# design.net
KiCad netlist of a schematic drawn in Altium Designer
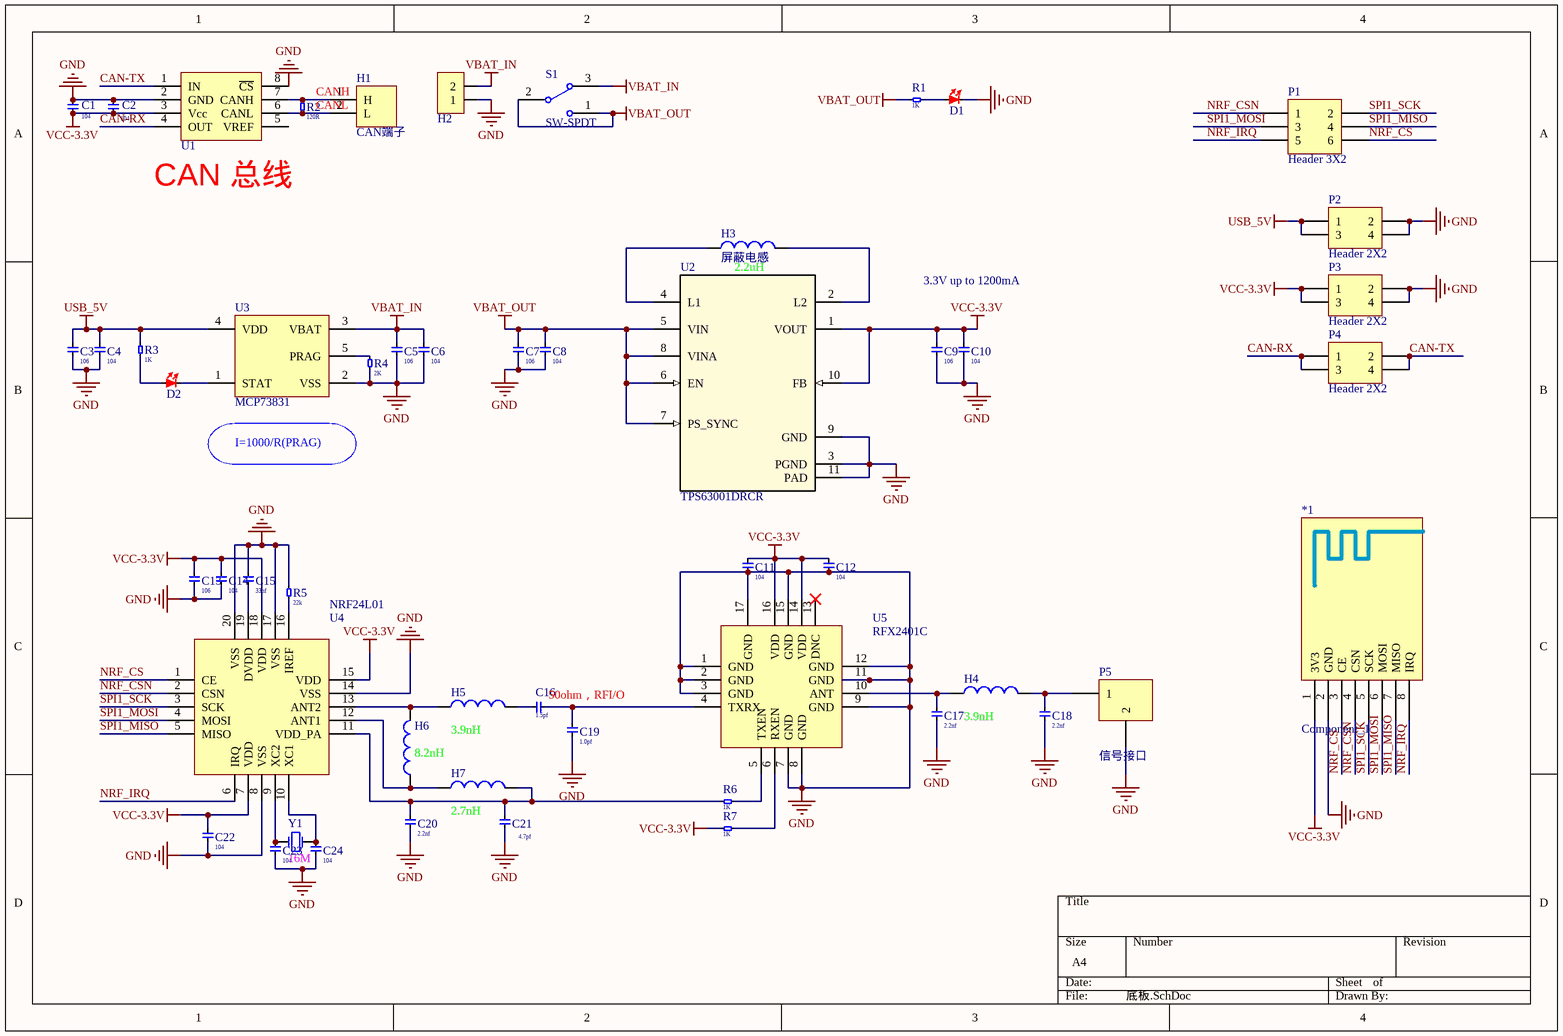
[diagram p0: 底板.SchDoc]

(export (version "E")
  (design (tool "Eeschema 10.0.6"))
  (components
    (comp (ref "*1")
      (value "Component_1")
      (footprint "PCBComponent_1")
      (libsource (lib "NRF2104") (part "Component_1"))
    )
    (comp (ref "C1")
      (value "CAP0603")
      (footprint "CAP0603")
      (fields (field (name "ALTIUM_UNNAMED_1") "104"))
      (libsource (lib "固执啊啊啊啊啊（方林的封装库）7.24") (part "CAP0603"))
    )
    (comp (ref "C2")
      (value "CAP0603")
      (footprint "CAP0603")
      (fields (field (name "ALTIUM_UNNAMED_1") "104"))
      (libsource (lib "固执啊啊啊啊啊（方林的封装库）7.24") (part "CAP0603"))
    )
    (comp (ref "C3")
      (value "CAP0603")
      (footprint "CAP0603")
      (fields (field (name "ALTIUM_UNNAMED_1") "106"))
      (libsource (lib "固执啊啊啊啊啊（方林的封装库）7.24") (part "CAP0603"))
    )
    (comp (ref "C4")
      (value "CAP0603")
      (footprint "CAP0603")
      (fields (field (name "ALTIUM_UNNAMED_1") "104"))
      (libsource (lib "固执啊啊啊啊啊（方林的封装库）7.24") (part "CAP0603"))
    )
    (comp (ref "C5")
      (value "CAP0603")
      (footprint "CAP0603")
      (fields (field (name "ALTIUM_UNNAMED_1") "106"))
      (libsource (lib "固执啊啊啊啊啊（方林的封装库）7.24") (part "CAP0603"))
    )
    (comp (ref "C6")
      (value "CAP0603")
      (footprint "CAP0603")
      (fields (field (name "ALTIUM_UNNAMED_1") "104"))
      (libsource (lib "固执啊啊啊啊啊（方林的封装库）7.24") (part "CAP0603"))
    )
    (comp (ref "C7")
      (value "CAP0603")
      (footprint "CAP0603")
      (fields (field (name "ALTIUM_UNNAMED_1") "106"))
      (libsource (lib "固执啊啊啊啊啊（方林的封装库）7.24") (part "CAP0603"))
    )
    (comp (ref "C8")
      (value "CAP0603")
      (footprint "CAP0603")
      (fields (field (name "ALTIUM_UNNAMED_1") "104"))
      (libsource (lib "固执啊啊啊啊啊（方林的封装库）7.24") (part "CAP0603"))
    )
    (comp (ref "C9")
      (value "CAP0603")
      (footprint "CAP0603")
      (fields (field (name "ALTIUM_UNNAMED_1") "106"))
      (libsource (lib "固执啊啊啊啊啊（方林的封装库）7.24") (part "CAP0603"))
    )
    (comp (ref "C10")
      (value "CAP0603")
      (footprint "CAP0603")
      (fields (field (name "ALTIUM_UNNAMED_1") "104"))
      (libsource (lib "固执啊啊啊啊啊（方林的封装库）7.24") (part "CAP0603"))
    )
    (comp (ref "C11")
      (value "CAP0603")
      (footprint "CAP0603")
      (fields (field (name "ALTIUM_UNNAMED_1") "104"))
      (libsource (lib "固执啊啊啊啊啊（方林的封装库）7.24") (part "CAP0603"))
    )
    (comp (ref "C12")
      (value "CAP0603")
      (footprint "CAP0603")
      (fields (field (name "ALTIUM_UNNAMED_1") "104"))
      (libsource (lib "固执啊啊啊啊啊（方林的封装库）7.24") (part "CAP0603"))
    )
    (comp (ref "C13")
      (value "CAP0603")
      (footprint "CAP0603")
      (fields (field (name "ALTIUM_UNNAMED_1") "106"))
      (libsource (lib "固执啊啊啊啊啊（方林的封装库）7.24") (part "CAP0603"))
    )
    (comp (ref "C14")
      (value "CAP0603")
      (footprint "CAP0603")
      (fields (field (name "ALTIUM_UNNAMED_1") "104"))
      (libsource (lib "固执啊啊啊啊啊（方林的封装库）7.24") (part "CAP0603"))
    )
    (comp (ref "C15")
      (value "CAP0603")
      (footprint "CAP0603")
      (fields (field (name "ALTIUM_UNNAMED_1") "33nf"))
      (libsource (lib "固执啊啊啊啊啊（方林的封装库）7.24") (part "CAP0603"))
    )
    (comp (ref "C16")
      (value "CAP0603")
      (footprint "CAP0603")
      (fields (field (name "ALTIUM_UNNAMED_1") "1.5pf"))
      (libsource (lib "固执啊啊啊啊啊（方林的封装库）7.24") (part "CAP0603"))
    )
    (comp (ref "C17")
      (value "CAP0603")
      (footprint "CAP0603")
      (fields (field (name "ALTIUM_UNNAMED_1") "2.2nf"))
      (libsource (lib "固执啊啊啊啊啊（方林的封装库）7.24") (part "CAP0603"))
    )
    (comp (ref "C18")
      (value "CAP0603")
      (footprint "CAP0603")
      (fields (field (name "ALTIUM_UNNAMED_1") "2.2nf"))
      (libsource (lib "固执啊啊啊啊啊（方林的封装库）7.24") (part "CAP0603"))
    )
    (comp (ref "C19")
      (value "CAP0603")
      (footprint "CAP0603")
      (fields (field (name "ALTIUM_UNNAMED_1") "1.0pf"))
      (libsource (lib "固执啊啊啊啊啊（方林的封装库）7.24") (part "CAP0603"))
    )
    (comp (ref "C20")
      (value "CAP0603")
      (footprint "CAP0603")
      (fields (field (name "ALTIUM_UNNAMED_1") "2.2nf"))
      (libsource (lib "固执啊啊啊啊啊（方林的封装库）7.24") (part "CAP0603"))
    )
    (comp (ref "C21")
      (value "CAP0603")
      (footprint "CAP0603")
      (fields (field (name "ALTIUM_UNNAMED_1") "4.7pf"))
      (libsource (lib "固执啊啊啊啊啊（方林的封装库）7.24") (part "CAP0603"))
    )
    (comp (ref "C22")
      (value "CAP0603")
      (footprint "CAP0603")
      (fields (field (name "ALTIUM_UNNAMED_1") "104"))
      (libsource (lib "固执啊啊啊啊啊（方林的封装库）7.24") (part "CAP0603"))
    )
    (comp (ref "C23")
      (value "CAP0603")
      (footprint "CAP0603")
      (fields (field (name "ALTIUM_UNNAMED_1") "104"))
      (libsource (lib "固执啊啊啊啊啊（方林的封装库）7.24") (part "CAP0603"))
    )
    (comp (ref "C24")
      (value "CAP0603")
      (footprint "CAP0603")
      (fields (field (name "ALTIUM_UNNAMED_1") "104"))
      (libsource (lib "固执啊啊啊啊啊（方林的封装库）7.24") (part "CAP0603"))
    )
    (comp (ref "D1")
      (value "LED")
      (footprint "LED_0603_B")
      (libsource (lib "固执啊啊啊啊啊（方林的封装库）7.24") (part "LED"))
    )
    (comp (ref "D2")
      (value "LED")
      (footprint "LED_0603_B")
      (libsource (lib "固执啊啊啊啊啊（方林的封装库）7.24") (part "LED"))
    )
    (comp (ref "H1")
      (value "CAN端子")
      (footprint "CAN端子")
      (libsource (lib "固执啊啊啊啊啊（方林的封装库）7.24") (part "CAN端子"))
    )
    (comp (ref "H2")
      (value "H2")
      (footprint "H2_WHITE")
      (description "排针")
      (libsource (lib "xiaoze_Library") (part "H2"))
    )
    (comp (ref "H3")
      (value "屏蔽电感")
      (footprint "屏蔽7.2*7.2")
      (fields (field (name "ALTIUM_UNNAMED_1") "2.2uH"))
      (libsource (lib "固执啊啊啊啊啊（方林的封装库）7.24") (part "屏蔽电感"))
    )
    (comp (ref "H4")
      (value "屏蔽电感")
      (footprint "CAP0603")
      (fields (field (name "ALTIUM_UNNAMED_1") "3.9nH"))
      (libsource (lib "固执啊啊啊啊啊（方林的封装库）7.24") (part "屏蔽电感"))
    )
    (comp (ref "H5")
      (value "屏蔽电感")
      (footprint "CAP0603")
      (fields (field (name "ALTIUM_UNNAMED_1") "3.9nH"))
      (libsource (lib "固执啊啊啊啊啊（方林的封装库）7.24") (part "屏蔽电感"))
    )
    (comp (ref "H6")
      (value "屏蔽电感")
      (footprint "CAP0603")
      (fields (field (name "ALTIUM_UNNAMED_1") "8.2nH"))
      (libsource (lib "固执啊啊啊啊啊（方林的封装库）7.24") (part "屏蔽电感"))
    )
    (comp (ref "H7")
      (value "屏蔽电感")
      (footprint "CAP0603")
      (fields (field (name "ALTIUM_UNNAMED_1") "2.7nH"))
      (libsource (lib "固执啊啊啊啊啊（方林的封装库）7.24") (part "屏蔽电感"))
    )
    (comp (ref "P1")
      (value "Header 3X2")
      (footprint "HDR2X3")
      (description "Header, 3-Pin, Dual row")
      (fields (field (name "PUBLISHER") "Altium Limited"))
      (libsource (lib "Miscellaneous Connectors") (part "Header 3X2"))
    )
    (comp (ref "P2")
      (value "Header 2X2")
      (footprint "HDR2X2")
      (description "Header, 2-Pin, Dual row")
      (fields (field (name "PUBLISHER") "Altium Limited"))
      (libsource (lib "Miscellaneous Connectors") (part "Header 2X2"))
    )
    (comp (ref "P3")
      (value "Header 2X2")
      (footprint "HDR2X2")
      (description "Header, 2-Pin, Dual row")
      (fields (field (name "PUBLISHER") "Altium Limited"))
      (libsource (lib "Miscellaneous Connectors") (part "Header 2X2"))
    )
    (comp (ref "P4")
      (value "Header 2X2")
      (footprint "HDR2X2")
      (description "Header, 2-Pin, Dual row")
      (fields (field (name "PUBLISHER") "Altium Limited"))
      (libsource (lib "Miscellaneous Connectors") (part "Header 2X2"))
    )
    (comp (ref "P5")
      (value "信号接口")
      (footprint "SMA-偏脚")
      (fields (field (name "PUBLISHER") "Altium Limited"))
      (libsource (lib "遥控器的封装") (part "SMA偏脚"))
    )
    (comp (ref "R1")
      (value "电阻R")
      (footprint "R0603")
      (fields (field (name "ALTIUM_UNNAMED_1") "1K"))
      (libsource (lib "固执啊啊啊啊啊（方林的封装库）7.24") (part "电阻R"))
    )
    (comp (ref "R2")
      (value "电阻R")
      (footprint "R0603")
      (fields (field (name "ALTIUM_UNNAMED_1") "120R"))
      (libsource (lib "固执啊啊啊啊啊（方林的封装库）7.24") (part "电阻R"))
    )
    (comp (ref "R3")
      (value "电阻R")
      (footprint "R0603")
      (fields (field (name "ALTIUM_UNNAMED_1") "1K"))
      (libsource (lib "固执啊啊啊啊啊（方林的封装库）7.24") (part "电阻R"))
    )
    (comp (ref "R4")
      (value "电阻R")
      (footprint "R0603")
      (fields (field (name "ALTIUM_UNNAMED_1") "2K"))
      (libsource (lib "固执啊啊啊啊啊（方林的封装库）7.24") (part "电阻R"))
    )
    (comp (ref "R5")
      (value "电阻R")
      (footprint "R0603")
      (fields (field (name "ALTIUM_UNNAMED_1") "22k"))
      (libsource (lib "固执啊啊啊啊啊（方林的封装库）7.24") (part "电阻R"))
    )
    (comp (ref "R6")
      (value "电阻R")
      (footprint "R0603")
      (fields (field (name "ALTIUM_UNNAMED_1") "1K"))
      (libsource (lib "固执啊啊啊啊啊（方林的封装库）7.24") (part "电阻R"))
    )
    (comp (ref "R7")
      (value "电阻R")
      (footprint "R0603")
      (fields (field (name "ALTIUM_UNNAMED_1") "1K"))
      (libsource (lib "固执啊啊啊啊啊（方林的封装库）7.24") (part "电阻R"))
    )
    (comp (ref "S1")
      (value "SW-SPDT")
      (footprint "SWITCH_A2")
      (description "开关")
      (fields (field (name "PUBLISHER") "Altium Limited"))
      (libsource (lib "Fszhang") (part "SW-SPDT"))
    )
    (comp (ref "U1")
      (value "VP230")
      (footprint "VP230")
      (description "CAN 芯片")
      (libsource (lib "固执啊啊啊啊啊（方林的封装库）7.24") (part "VP230"))
    )
    (comp (ref "U2")
      (value "TPS63001DRCR")
      (footprint "TPS63001")
      (description "Imported")
      (fields
        (field (name "ALTERNATE_PARTNUMBER") "TPS63001DRCT")
        (field (name "MANUFACTURER") "Texas Instruments")
      )
      (libsource (lib "遥控器的封装") (part "TPS63001DRCR"))
    )
    (comp (ref "U3") (value "MCP73831") (footprint "SOT-23-5") (libsource (lib "遥控器的封装") (part "MCP73831")))
    (comp (ref "U4")
      (value "NRF24L01")
      (footprint "QFN50P400X400X85_HS-21N")
      (libsource (lib "遥控器的封装") (part "NRF24L01_1"))
    )
    (comp (ref "U5")
      (value "RFX2401C")
      (footprint "QFN50P300X300X55_HS-17N")
      (libsource (lib "遥控器的封装") (part "RFX2401C"))
    )
    (comp (ref "Y1")
      (value "XTAL")
      (footprint "XTAL")
      (description "晶振")
      (fields (field (name "ALTIUM_UNNAMED_1") "16M"))
      (libsource (lib "固执啊啊啊啊啊（方林的封装库）7.24") (part "XTAL"))
    )
  )
  (nets
    (net (code "1") (name "/CAN-RX") (class "Default")
      (node (ref "P4") (pin "1") (pinfunction "1_1") (pintype "passive"))
      (node (ref "P4") (pin "3") (pinfunction "3_3") (pintype "passive"))
      (node (ref "U1") (pin "4") (pinfunction "OUT_4") (pintype "passive"))
    )
    (net (code "2") (name "/CAN-TX") (class "Default")
      (node (ref "P4") (pin "2") (pinfunction "2_2") (pintype "passive"))
      (node (ref "P4") (pin "4") (pinfunction "4_4") (pintype "passive"))
      (node (ref "U1") (pin "1") (pinfunction "IN_1") (pintype "passive"))
    )
    (net (code "3") (name "/CANH") (class "Default")
      (node (ref "H1") (pin "1") (pinfunction "H_1") (pintype "passive"))
      (node (ref "R2") (pin "2") (pintype "passive"))
      (node (ref "U1") (pin "7") (pinfunction "CANH_7") (pintype "passive"))
    )
    (net (code "4") (name "/CANL") (class "Default")
      (node (ref "H1") (pin "2") (pinfunction "L_2") (pintype "passive"))
      (node (ref "R2") (pin "1") (pintype "passive"))
      (node (ref "U1") (pin "6") (pinfunction "CANL_6") (pintype "passive"))
    )
    (net (code "5") (name "/NRF_CS") (class "Default")
      (node (ref "*1") (pin "3") (pinfunction "CE_3") (pintype "passive"))
      (node (ref "P1") (pin "6") (pinfunction "6_6") (pintype "passive"))
      (node (ref "U4") (pin "1") (pinfunction "CE_1") (pintype "passive"))
    )
    (net (code "6") (name "/NRF_CSN") (class "Default")
      (node (ref "*1") (pin "4") (pinfunction "CSN_4") (pintype "passive"))
      (node (ref "P1") (pin "1") (pinfunction "1_1") (pintype "passive"))
      (node (ref "U4") (pin "2") (pinfunction "CSN_2") (pintype "passive"))
    )
    (net (code "7") (name "/NRF_IRQ") (class "Default")
      (node (ref "*1") (pin "8") (pinfunction "IRQ_8") (pintype "passive"))
      (node (ref "P1") (pin "5") (pinfunction "5_5") (pintype "passive"))
      (node (ref "U4") (pin "6") (pinfunction "IRQ_6") (pintype "passive"))
    )
    (net (code "8") (name "/SPI1_MISO") (class "Default")
      (node (ref "*1") (pin "7") (pinfunction "MISO_7") (pintype "passive"))
      (node (ref "P1") (pin "4") (pinfunction "4_4") (pintype "passive"))
      (node (ref "U4") (pin "5") (pinfunction "MISO_5") (pintype "passive"))
    )
    (net (code "9") (name "/SPI1_MOSI") (class "Default")
      (node (ref "*1") (pin "6") (pinfunction "MOSI_6") (pintype "passive"))
      (node (ref "P1") (pin "3") (pinfunction "3_3") (pintype "passive"))
      (node (ref "U4") (pin "4") (pinfunction "MOSI_4") (pintype "passive"))
    )
    (net (code "10") (name "/SPI1_SCK") (class "Default")
      (node (ref "*1") (pin "5") (pinfunction "SCK_5") (pintype "passive"))
      (node (ref "P1") (pin "2") (pinfunction "2_2") (pintype "passive"))
      (node (ref "U4") (pin "3") (pinfunction "SCK_3") (pintype "passive"))
    )
    (net (code "11") (name "GND") (class "Default")
      (node (ref "*1") (pin "2") (pinfunction "GND_2") (pintype "passive"))
      (node (ref "C1") (pin "2") (pinfunction "2_2") (pintype "passive"))
      (node (ref "C10") (pin "1") (pinfunction "1_1") (pintype "passive"))
      (node (ref "C11") (pin "1") (pinfunction "1_1") (pintype "passive"))
      (node (ref "C12") (pin "1") (pinfunction "1_1") (pintype "passive"))
      (node (ref "C13") (pin "1") (pinfunction "1_1") (pintype "passive"))
      (node (ref "C14") (pin "1") (pinfunction "1_1") (pintype "passive"))
      (node (ref "C15") (pin "2") (pinfunction "2_2") (pintype "passive"))
      (node (ref "C17") (pin "1") (pinfunction "1_1") (pintype "passive"))
      (node (ref "C18") (pin "1") (pinfunction "1_1") (pintype "passive"))
      (node (ref "C19") (pin "2") (pinfunction "2_2") (pintype "passive"))
      (node (ref "C2") (pin "2") (pinfunction "2_2") (pintype "passive"))
      (node (ref "C20") (pin "2") (pinfunction "2_2") (pintype "passive"))
      (node (ref "C21") (pin "2") (pinfunction "2_2") (pintype "passive"))
      (node (ref "C22") (pin "1") (pinfunction "1_1") (pintype "passive"))
      (node (ref "C23") (pin "1") (pinfunction "1_1") (pintype "passive"))
      (node (ref "C24") (pin "1") (pinfunction "1_1") (pintype "passive"))
      (node (ref "C3") (pin "1") (pinfunction "1_1") (pintype "passive"))
      (node (ref "C4") (pin "1") (pinfunction "1_1") (pintype "passive"))
      (node (ref "C5") (pin "1") (pinfunction "1_1") (pintype "passive"))
      (node (ref "C6") (pin "1") (pinfunction "1_1") (pintype "passive"))
      (node (ref "C7") (pin "1") (pinfunction "1_1") (pintype "passive"))
      (node (ref "C8") (pin "1") (pinfunction "1_1") (pintype "passive"))
      (node (ref "C9") (pin "1") (pinfunction "1_1") (pintype "passive"))
      (node (ref "D1") (pin "2") (pintype "passive"))
      (node (ref "H2") (pin "1") (pinfunction "1_1") (pintype "passive"))
      (node (ref "P2") (pin "2") (pinfunction "2_2") (pintype "passive"))
      (node (ref "P2") (pin "4") (pinfunction "4_4") (pintype "passive"))
      (node (ref "P3") (pin "2") (pinfunction "2_2") (pintype "passive"))
      (node (ref "P3") (pin "4") (pinfunction "4_4") (pintype "passive"))
      (node (ref "P5") (pin "2") (pinfunction "2_2") (pintype "passive"))
      (node (ref "R4") (pin "1") (pintype "passive"))
      (node (ref "R5") (pin "2") (pintype "passive"))
      (node (ref "U1") (pin "2") (pinfunction "GND_2") (pintype "passive"))
      (node (ref "U1") (pin "8") (pinfunction "~{CS}_8") (pintype "passive"))
      (node (ref "U2") (pin "11") (pinfunction "PAD_11") (pintype "power_in"))
      (node (ref "U2") (pin "3") (pinfunction "PGND_3") (pintype "power_in"))
      (node (ref "U2") (pin "9") (pinfunction "GND_9") (pintype "power_in"))
      (node (ref "U3") (pin "2") (pinfunction "VSS_2") (pintype "passive"))
      (node (ref "U4") (pin "14") (pinfunction "VSS_14") (pintype "passive"))
      (node (ref "U4") (pin "17") (pinfunction "VSS_17") (pintype "passive"))
      (node (ref "U4") (pin "20") (pinfunction "VSS_20") (pintype "passive"))
      (node (ref "U4") (pin "8") (pinfunction "VSS_8") (pintype "passive"))
      (node (ref "U5") (pin "1") (pinfunction "GND_1") (pintype "passive"))
      (node (ref "U5") (pin "11") (pinfunction "GND_11") (pintype "passive"))
      (node (ref "U5") (pin "12") (pinfunction "GND_12") (pintype "passive"))
      (node (ref "U5") (pin "15") (pinfunction "GND_15") (pintype "passive"))
      (node (ref "U5") (pin "17") (pinfunction "GND_17") (pintype "passive"))
      (node (ref "U5") (pin "2") (pinfunction "GND_2") (pintype "passive"))
      (node (ref "U5") (pin "3") (pinfunction "GND_3") (pintype "passive"))
      (node (ref "U5") (pin "7") (pinfunction "GND_7") (pintype "passive"))
      (node (ref "U5") (pin "8") (pinfunction "GND_8") (pintype "passive"))
      (node (ref "U5") (pin "9") (pinfunction "GND_9") (pintype "passive"))
    )
    (net (code "12") (name "Net-(C16-Pad2)") (class "Default")
      (node (ref "C16") (pin "2") (pinfunction "2_2") (pintype "passive"))
      (node (ref "H5") (pin "2") (pinfunction "2_2") (pintype "passive"))
    )
    (net (code "13") (name "Net-(C18-Pad2)") (class "Default")
      (node (ref "C18") (pin "2") (pinfunction "2_2") (pintype "passive"))
      (node (ref "H4") (pin "2") (pinfunction "2_2") (pintype "passive"))
      (node (ref "P5") (pin "1") (pinfunction "1_1") (pintype "passive"))
    )
    (net (code "14") (name "Net-(D1-Pad1)") (class "Default")
      (node (ref "D1") (pin "1") (pintype "passive"))
      (node (ref "R1") (pin "1") (pintype "passive"))
    )
    (net (code "15") (name "Net-(D2-Pad1)") (class "Default")
      (node (ref "D2") (pin "1") (pintype "passive"))
      (node (ref "R3") (pin "1") (pintype "passive"))
    )
    (net (code "16") (name "Net-(U2-L1)") (class "Default")
      (node (ref "H3") (pin "1") (pinfunction "1_1") (pintype "passive"))
      (node (ref "U2") (pin "4") (pinfunction "L1_4") (pintype "passive"))
    )
    (net (code "17") (name "Net-(U2-L2)") (class "Default")
      (node (ref "H3") (pin "2") (pinfunction "2_2") (pintype "passive"))
      (node (ref "U2") (pin "2") (pinfunction "L2_2") (pintype "passive"))
    )
    (net (code "18") (name "Net-(U3-PRAG)") (class "Default")
      (node (ref "R4") (pin "2") (pintype "passive"))
      (node (ref "U3") (pin "5") (pinfunction "PRAG_5") (pintype "passive"))
    )
    (net (code "19") (name "Net-(U3-STAT)") (class "Default")
      (node (ref "D2") (pin "2") (pintype "passive"))
      (node (ref "U3") (pin "1") (pinfunction "STAT_1") (pintype "passive"))
    )
    (net (code "20") (name "Net-(U4-ANT1)") (class "Default")
      (node (ref "H6") (pin "1") (pinfunction "1_1") (pintype "passive"))
      (node (ref "H7") (pin "1") (pinfunction "1_1") (pintype "passive"))
      (node (ref "U4") (pin "12") (pinfunction "ANT1_12") (pintype "passive"))
    )
    (net (code "21") (name "Net-(U4-ANT2)") (class "Default")
      (node (ref "H5") (pin "1") (pinfunction "1_1") (pintype "passive"))
      (node (ref "H6") (pin "2") (pinfunction "2_2") (pintype "passive"))
      (node (ref "U4") (pin "13") (pinfunction "ANT2_13") (pintype "passive"))
    )
    (net (code "22") (name "Net-(U4-DVDD)") (class "Default")
      (node (ref "C15") (pin "1") (pinfunction "1_1") (pintype "passive"))
      (node (ref "U4") (pin "19") (pinfunction "DVDD_19") (pintype "passive"))
    )
    (net (code "23") (name "Net-(U4-IREF)") (class "Default")
      (node (ref "R5") (pin "1") (pintype "passive"))
      (node (ref "U4") (pin "16") (pinfunction "IREF_16") (pintype "passive"))
    )
    (net (code "24") (name "Net-(U4-VDD_PA)") (class "Default")
      (node (ref "C20") (pin "1") (pinfunction "1_1") (pintype "passive"))
      (node (ref "C21") (pin "1") (pinfunction "1_1") (pintype "passive"))
      (node (ref "H7") (pin "2") (pinfunction "2_2") (pintype "passive"))
      (node (ref "R6") (pin "2") (pintype "passive"))
      (node (ref "U4") (pin "11") (pinfunction "VDD_PA_11") (pintype "passive"))
    )
    (net (code "25") (name "Net-(U4-XC1)") (class "Default")
      (node (ref "C24") (pin "2") (pinfunction "2_2") (pintype "passive"))
      (node (ref "U4") (pin "10") (pinfunction "XC1_10") (pintype "passive"))
      (node (ref "Y1") (pin "2") (pinfunction "OSC2_2") (pintype "passive"))
    )
    (net (code "26") (name "Net-(U4-XC2)") (class "Default")
      (node (ref "C23") (pin "2") (pinfunction "2_2") (pintype "passive"))
      (node (ref "U4") (pin "9") (pinfunction "XC2_9") (pintype "passive"))
      (node (ref "Y1") (pin "1") (pinfunction "OSC1_1") (pintype "passive"))
    )
    (net (code "27") (name "Net-(U5-ANT)") (class "Default")
      (node (ref "C17") (pin "2") (pinfunction "2_2") (pintype "passive"))
      (node (ref "H4") (pin "1") (pinfunction "1_1") (pintype "passive"))
      (node (ref "U5") (pin "10") (pinfunction "ANT_10") (pintype "passive"))
    )
    (net (code "28") (name "Net-(U5-RXEN)") (class "Default")
      (node (ref "R7") (pin "1") (pintype "passive"))
      (node (ref "U5") (pin "6") (pinfunction "RXEN_6") (pintype "passive"))
    )
    (net (code "29") (name "Net-(U5-TXEN)") (class "Default")
      (node (ref "R6") (pin "1") (pintype "passive"))
      (node (ref "U5") (pin "5") (pinfunction "TXEN_5") (pintype "passive"))
    )
    (net (code "30") (name "Net-(U5-TXRX)") (class "Default")
      (node (ref "C16") (pin "1") (pinfunction "1_1") (pintype "passive"))
      (node (ref "C19") (pin "1") (pinfunction "1_1") (pintype "passive"))
      (node (ref "U5") (pin "4") (pinfunction "TXRX_4") (pintype "passive"))
    )
    (net (code "31") (name "USB_5V") (class "Default")
      (node (ref "C3") (pin "2") (pinfunction "2_2") (pintype "passive"))
      (node (ref "C4") (pin "2") (pinfunction "2_2") (pintype "passive"))
      (node (ref "P2") (pin "1") (pinfunction "1_1") (pintype "passive"))
      (node (ref "P2") (pin "3") (pinfunction "3_3") (pintype "passive"))
      (node (ref "R3") (pin "2") (pintype "passive"))
      (node (ref "U3") (pin "4") (pinfunction "VDD_4") (pintype "passive"))
    )
    (net (code "32") (name "VBAT_IN") (class "Default")
      (node (ref "C5") (pin "2") (pinfunction "2_2") (pintype "passive"))
      (node (ref "C6") (pin "2") (pinfunction "2_2") (pintype "passive"))
      (node (ref "H2") (pin "2") (pinfunction "2_2") (pintype "passive"))
      (node (ref "S1") (pin "3") (pinfunction "3_3") (pintype "passive"))
      (node (ref "U3") (pin "3") (pinfunction "VBAT_3") (pintype "passive"))
    )
    (net (code "33") (name "VBAT_OUT") (class "Default")
      (node (ref "C7") (pin "2") (pinfunction "2_2") (pintype "passive"))
      (node (ref "C8") (pin "2") (pinfunction "2_2") (pintype "passive"))
      (node (ref "R1") (pin "2") (pintype "passive"))
      (node (ref "S1") (pin "1") (pinfunction "1_1") (pintype "passive"))
      (node (ref "S1") (pin "2") (pinfunction "2_2") (pintype "passive"))
      (node (ref "U2") (pin "5") (pinfunction "VIN_5") (pintype "power_in"))
      (node (ref "U2") (pin "6") (pinfunction "EN_6") (pintype "input"))
      (node (ref "U2") (pin "7") (pinfunction "PS_SYNC_7") (pintype "input"))
      (node (ref "U2") (pin "8") (pinfunction "VINA_8") (pintype "power_in"))
    )
    (net (code "34") (name "VCC-3.3V") (class "Default")
      (node (ref "*1") (pin "1") (pinfunction "3V3_1") (pintype "passive"))
      (node (ref "C1") (pin "1") (pinfunction "1_1") (pintype "passive"))
      (node (ref "C10") (pin "2") (pinfunction "2_2") (pintype "passive"))
      (node (ref "C11") (pin "2") (pinfunction "2_2") (pintype "passive"))
      (node (ref "C12") (pin "2") (pinfunction "2_2") (pintype "passive"))
      (node (ref "C13") (pin "2") (pinfunction "2_2") (pintype "passive"))
      (node (ref "C14") (pin "2") (pinfunction "2_2") (pintype "passive"))
      (node (ref "C2") (pin "1") (pinfunction "1_1") (pintype "passive"))
      (node (ref "C22") (pin "2") (pinfunction "2_2") (pintype "passive"))
      (node (ref "C9") (pin "2") (pinfunction "2_2") (pintype "passive"))
      (node (ref "P3") (pin "1") (pinfunction "1_1") (pintype "passive"))
      (node (ref "P3") (pin "3") (pinfunction "3_3") (pintype "passive"))
      (node (ref "R7") (pin "2") (pintype "passive"))
      (node (ref "U1") (pin "3") (pinfunction "Vcc_3") (pintype "passive"))
      (node (ref "U2") (pin "1") (pinfunction "VOUT_1") (pintype "power_in"))
      (node (ref "U2") (pin "10") (pinfunction "FB_10") (pintype "input"))
      (node (ref "U4") (pin "15") (pinfunction "VDD_15") (pintype "passive"))
      (node (ref "U4") (pin "18") (pinfunction "VDD_18") (pintype "passive"))
      (node (ref "U4") (pin "7") (pinfunction "VDD_7") (pintype "passive"))
      (node (ref "U5") (pin "14") (pinfunction "VDD_14") (pintype "passive"))
      (node (ref "U5") (pin "16") (pinfunction "VDD_16") (pintype "passive"))
    )
    (net (code "35") (name "unconnected-(U1-VREF-Pad5)") (class "Default")
      (node (ref "U1") (pin "5") (pinfunction "VREF_5") (pintype "passive"))
    )
    (net (code "36") (name "unconnected-(U5-DNC-Pad13)") (class "Default")
      (node (ref "U5") (pin "13") (pinfunction "DNC_13") (pintype "passive+no_connect"))
    )
  )
)
